# ESC.net
KiCad netlist of a schematic drawn in Altium Designer
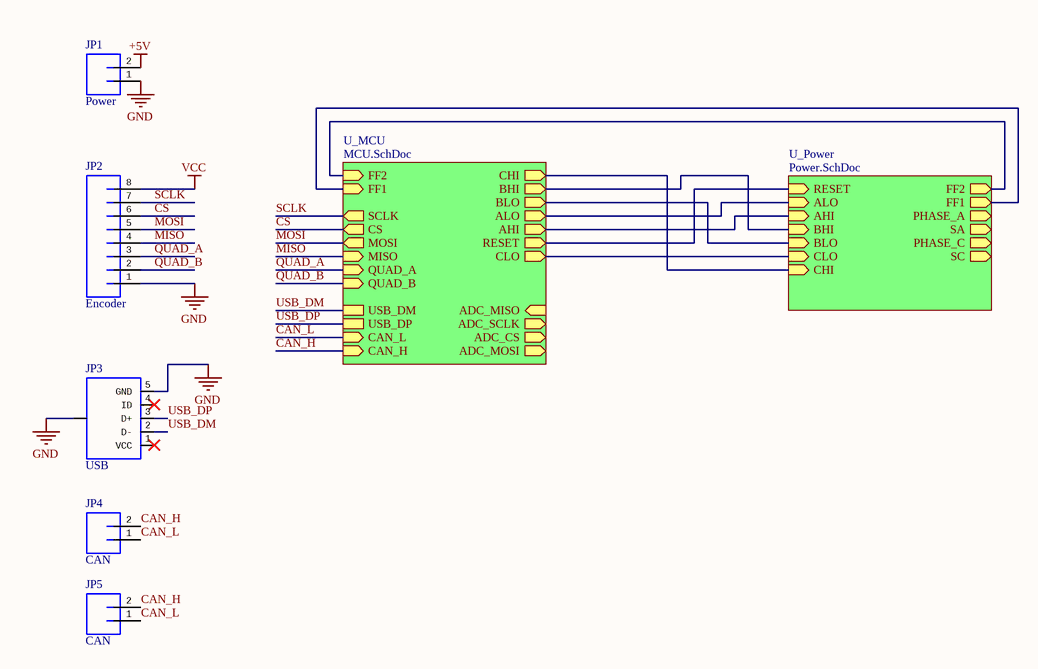
[diagram p0: ESC.SchDoc]

(export (version "E")
  (design (tool "Eeschema 10.0.6"))
  (components
    (comp (ref "JP1")
      (value "Power")
      (footprint "JST-2-PTH-VERT")
      (libsource (lib "Components") (part "JST_2_VERT"))
    )
    (comp (ref "JP2")
      (value "Encoder")
      (footprint "JST-8-PTH-VERT")
      (libsource (lib "Components") (part "JST_8_VERT"))
    )
    (comp (ref "JP3")
      (value "USB")
      (footprint "USB-MICROB")
      (libsource (lib "Components") (part "USB_MICROB_PLUG-SMT"))
    )
    (comp (ref "JP4")
      (value "CAN")
      (footprint "JST-2-PTH-VERT")
      (libsource (lib "Components") (part "JST_2_VERT"))
    )
    (comp (ref "JP5")
      (value "CAN")
      (footprint "JST-2-PTH-VERT")
      (libsource (lib "Components") (part "JST_2_VERT"))
    )
  )
  (nets
    (net (code "1") (name "+5V") (class "Default")
      (node (ref "JP1") (pin "2") (pinfunction "2_2") (pintype "passive"))
    )
    (net (code "10") (name "/CAN_H") (class "Default")
      (node (ref "JP4") (pin "2") (pinfunction "2_2") (pintype "passive"))
      (node (ref "JP5") (pin "2") (pinfunction "2_2") (pintype "passive"))
    )
    (net (code "11") (name "/CAN_L") (class "Default")
      (node (ref "JP4") (pin "1") (pinfunction "1_1") (pintype "passive"))
      (node (ref "JP5") (pin "1") (pinfunction "1_1") (pintype "passive"))
    )
    (net (code "14") (name "/CS") (class "Default")
      (node (ref "JP2") (pin "6") (pinfunction "6_6") (pintype "passive"))
    )
    (net (code "17") (name "/MISO") (class "Default")
      (node (ref "JP2") (pin "4") (pinfunction "4_4") (pintype "passive"))
    )
    (net (code "18") (name "/MOSI") (class "Default")
      (node (ref "JP2") (pin "5") (pinfunction "5_5") (pintype "passive"))
    )
    (net (code "21") (name "/QUAD_A") (class "Default")
      (node (ref "JP2") (pin "3") (pinfunction "3_3") (pintype "passive"))
    )
    (net (code "22") (name "/QUAD_B") (class "Default")
      (node (ref "JP2") (pin "2") (pinfunction "2_2") (pintype "passive"))
    )
    (net (code "26") (name "/SCLK") (class "Default")
      (node (ref "JP2") (pin "7") (pinfunction "7_7") (pintype "passive"))
    )
    (net (code "27") (name "/USB_DM") (class "Default")
      (node (ref "JP3") (pin "2") (pinfunction "D-_2") (pintype "passive"))
    )
    (net (code "28") (name "/USB_DP") (class "Default")
      (node (ref "JP3") (pin "3") (pinfunction "D+_3") (pintype "passive"))
    )
    (net (code "29") (name "GND") (class "Default")
      (node (ref "JP1") (pin "1") (pinfunction "1_1") (pintype "passive"))
      (node (ref "JP2") (pin "1") (pinfunction "1_1") (pintype "passive"))
      (node (ref "JP3") (pin "5") (pinfunction "GND_5") (pintype "passive"))
      (node (ref "JP3") (pin "6") (pinfunction "SHIELD_6") (pintype "passive"))
    )
    (net (code "30") (name "VCC") (class "Default")
      (node (ref "JP2") (pin "8") (pinfunction "8_8") (pintype "passive"))
    )
    (net (code "31") (name "unconnected-(JP3-ID-Pad4)") (class "Default")
      (node (ref "JP3") (pin "4") (pinfunction "ID_4") (pintype "passive+no_connect"))
    )
    (net (code "32") (name "unconnected-(JP3-VCC-Pad1)") (class "Default")
      (node (ref "JP3") (pin "1") (pinfunction "VCC_1") (pintype "passive+no_connect"))
    )
  )
)
